# Main.net
KiCad netlist of a schematic drawn in Altium Designer
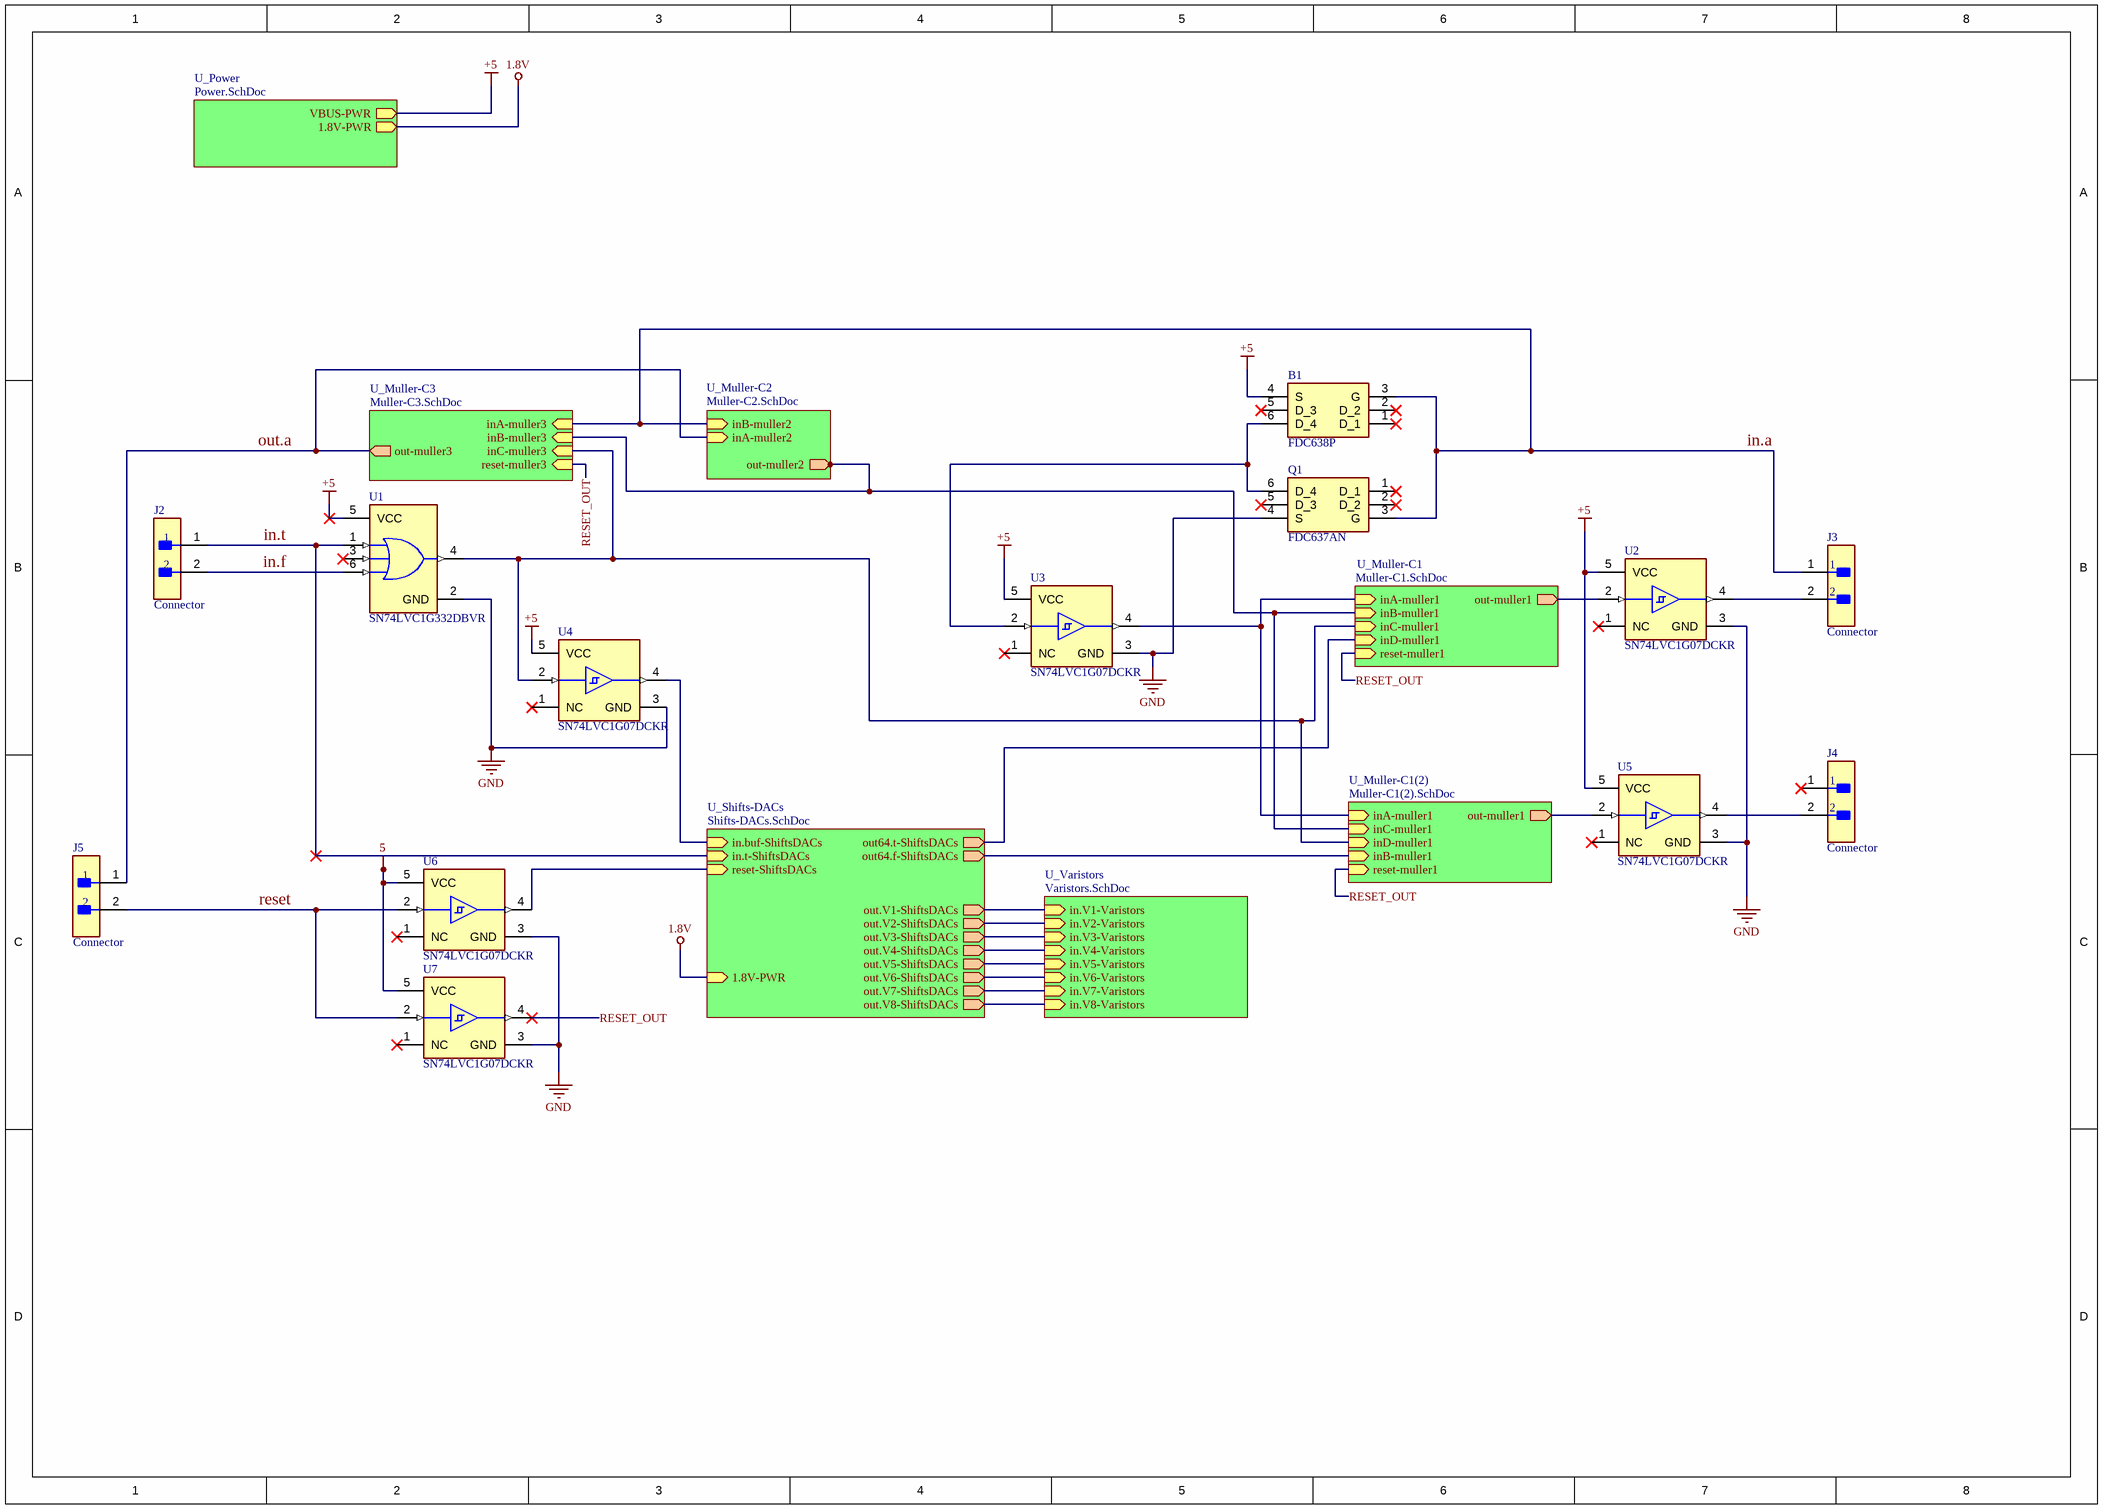
[diagram p0: Main.SchDoc]

(export (version "E")
  (design (tool "Eeschema 10.0.6"))
  (components
    (comp (ref "B1")
      (value "FDC638P")
      (footprint "SOT95P275X110-6N")
      (description "Low gate charge (10 nC typical)")
      (fields (field (name "MOUSER PART NUMBER") "512-FDC638P"))
      (libsource (lib "iloke") (part "FDC638P"))
    )
    (comp (ref "J2")
      (value "Connector")
      (footprint "FP-B2B-XH-A_LF_SN-MFG")
      (description "B2B-XH-A(LF)(SN) CONN HEADER VERT 2POS 2.5MM")
      (libsource (lib "") (part "3bc925449376181038e59eaffc5286c_1"))
    )
    (comp (ref "J3")
      (value "Connector")
      (footprint "FP-B2B-XH-A_LF_SN-MFG")
      (description "B2B-XH-A(LF)(SN) CONN HEADER VERT 2POS 2.5MM")
      (libsource (lib "Altium Content Vault") (part "3bc925449376181038e59eaffc5286c"))
    )
    (comp (ref "J4")
      (value "Connector")
      (footprint "FP-B2B-XH-A_LF_SN-MFG")
      (description "B2B-XH-A(LF)(SN) CONN HEADER VERT 2POS 2.5MM")
      (libsource (lib "Altium Content Vault") (part "3bc925449376181038e59eaffc5286c"))
    )
    (comp (ref "J5")
      (value "Connector")
      (footprint "FP-B2B-XH-A_LF_SN-MFG")
      (description "B2B-XH-A(LF)(SN) CONN HEADER VERT 2POS 2.5MM")
      (libsource (lib "") (part "3bc925449376181038e59eaffc5286c_1"))
    )
    (comp (ref "Q1")
      (value "FDC637AN")
      (footprint "SOT95P275X110-6N")
      (description "Low gate charge (10.5nC typical).")
      (fields (field (name "MOUSER PART NUMBER") "512-FDC637AN"))
      (libsource (lib "iloke") (part "FDC637AN"))
    )
    (comp (ref "U1")
      (value "SN74LVC1G332DBVR")
      (footprint "FP-DBV0006A-MFG")
      (description "IC GATE OR 1CH 3-INP SOT23-6")
      (fields
        (field (name "OCTOPART") "https://octopart.com/sn74lvc1g332dbvr-texas+instruments-464996")
        (field (name "MANUFACTURER") "TEXAS INSTRUMENTS")
      )
      (libsource (lib "Altium Content Vault") (part "9bd6587d4ded7f3f3ab4f7d0d680d6b"))
    )
    (comp (ref "U2")
      (value "SN74LVC1G07DCKR")
      (footprint "FP-DCK0005A-MFG")
      (description "Buffer, LVC/LCX/Z Series, 1-Func, 1-Input, CMOS, PDSO5")
      (libsource (lib "iloke") (part "8ab337023d36144ede9cc3383aed264"))
    )
    (comp (ref "U3")
      (value "SN74LVC1G07DCKR")
      (footprint "FP-DCK0005A-MFG")
      (description "Buffer, LVC/LCX/Z Series, 1-Func, 1-Input, CMOS, PDSO5")
      (libsource (lib "iloke") (part "8ab337023d36144ede9cc3383aed264"))
    )
    (comp (ref "U4")
      (value "SN74LVC1G07DCKR")
      (footprint "FP-DCK0005A-MFG")
      (description "Buffer, LVC/LCX/Z Series, 1-Func, 1-Input, CMOS, PDSO5")
      (libsource (lib "iloke") (part "8ab337023d36144ede9cc3383aed264"))
    )
    (comp (ref "U5")
      (value "SN74LVC1G07DCKR")
      (footprint "FP-DCK0005A-MFG")
      (description "Buffer, LVC/LCX/Z Series, 1-Func, 1-Input, CMOS, PDSO5")
      (libsource (lib "iloke") (part "8ab337023d36144ede9cc3383aed264"))
    )
    (comp (ref "U6")
      (value "SN74LVC1G07DCKR")
      (footprint "FP-DCK0005A-MFG")
      (description "Buffer, LVC/LCX/Z Series, 1-Func, 1-Input, CMOS, PDSO5")
      (libsource (lib "iloke") (part "8ab337023d36144ede9cc3383aed264"))
    )
    (comp (ref "U7")
      (value "SN74LVC1G07DCKR")
      (footprint "FP-DCK0005A-MFG")
      (description "Buffer, LVC/LCX/Z Series, 1-Func, 1-Input, CMOS, PDSO5")
      (libsource (lib "iloke") (part "8ab337023d36144ede9cc3383aed264"))
    )
  )
  (nets
    (net (code "1") (name "+5") (class "Default")
      (node (ref "B1") (pin "4") (pinfunction "S_4") (pintype "passive"))
      (node (ref "U1") (pin "5") (pinfunction "VCC_5") (pintype "power_in"))
      (node (ref "U2") (pin "5") (pinfunction "VCC_5") (pintype "power_in"))
      (node (ref "U3") (pin "5") (pinfunction "VCC_5") (pintype "power_in"))
      (node (ref "U4") (pin "5") (pinfunction "VCC_5") (pintype "power_in"))
      (node (ref "U5") (pin "5") (pinfunction "VCC_5") (pintype "power_in"))
    )
    (net (code "2") (name "/RESET_OUT") (class "Default")
      (node (ref "U7") (pin "4") (pinfunction "Y_4") (pintype "output"))
    )
    (net (code "3") (name "/in.a") (class "Default")
      (node (ref "B1") (pin "3") (pinfunction "G_3") (pintype "passive"))
      (node (ref "J3") (pin "1") (pinfunction "1_1") (pintype "passive"))
      (node (ref "Q1") (pin "3") (pinfunction "G_3") (pintype "passive"))
    )
    (net (code "4") (name "/in.buf-ShiftsDACs") (class "Default")
      (node (ref "U4") (pin "4") (pinfunction "Y_4") (pintype "output"))
    )
    (net (code "5") (name "/in.f") (class "Default")
      (node (ref "J2") (pin "2") (pinfunction "2_2") (pintype "passive"))
      (node (ref "U1") (pin "6") (pinfunction "C_6") (pintype "input"))
    )
    (net (code "6") (name "/in.t") (class "Default")
      (node (ref "J2") (pin "1") (pinfunction "1_1") (pintype "passive"))
      (node (ref "U1") (pin "1") (pinfunction "A_1") (pintype "input"))
    )
    (net (code "7") (name "/inA-muller1") (class "Default")
      (node (ref "U3") (pin "4") (pinfunction "Y_4") (pintype "output"))
    )
    (net (code "8") (name "/inC-muller1") (class "Default")
      (node (ref "U1") (pin "4") (pinfunction "Y_4") (pintype "output"))
      (node (ref "U4") (pin "2") (pinfunction "A_2") (pintype "input"))
    )
    (net (code "9") (name "/out-muller1") (class "Default")
      (node (ref "U2") (pin "2") (pinfunction "A_2") (pintype "input"))
    )
    (net (code "10") (name "/out-muller1_1") (class "Default")
      (node (ref "U5") (pin "2") (pinfunction "A_2") (pintype "input"))
    )
    (net (code "20") (name "/out.a") (class "Default")
      (node (ref "J5") (pin "1") (pinfunction "1_1") (pintype "passive"))
    )
    (net (code "23") (name "/reset") (class "Default")
      (node (ref "J5") (pin "2") (pinfunction "2_2") (pintype "passive"))
      (node (ref "U6") (pin "2") (pinfunction "A_2") (pintype "input"))
      (node (ref "U7") (pin "2") (pinfunction "A_2") (pintype "input"))
    )
    (net (code "24") (name "/reset-ShiftsDACs") (class "Default")
      (node (ref "U6") (pin "4") (pinfunction "Y_4") (pintype "output"))
    )
    (net (code "26") (name "5") (class "Default")
      (node (ref "U6") (pin "5") (pinfunction "VCC_5") (pintype "power_in"))
      (node (ref "U7") (pin "5") (pinfunction "VCC_5") (pintype "power_in"))
    )
    (net (code "27") (name "GND") (class "Default")
      (node (ref "Q1") (pin "4") (pinfunction "S_4") (pintype "passive"))
      (node (ref "U1") (pin "2") (pinfunction "GND_2") (pintype "power_in"))
      (node (ref "U2") (pin "3") (pinfunction "GND_3") (pintype "power_in"))
      (node (ref "U3") (pin "3") (pinfunction "GND_3") (pintype "power_in"))
      (node (ref "U4") (pin "3") (pinfunction "GND_3") (pintype "power_in"))
      (node (ref "U5") (pin "3") (pinfunction "GND_3") (pintype "power_in"))
      (node (ref "U6") (pin "3") (pinfunction "GND_3") (pintype "power_in"))
      (node (ref "U7") (pin "3") (pinfunction "GND_3") (pintype "power_in"))
    )
    (net (code "28") (name "Net-(B1-D_4)") (class "Default")
      (node (ref "B1") (pin "6") (pinfunction "D_4_6") (pintype "passive"))
      (node (ref "Q1") (pin "6") (pinfunction "D_4_6") (pintype "passive"))
      (node (ref "U3") (pin "2") (pinfunction "A_2") (pintype "input"))
    )
    (net (code "29") (name "Net-(U2-Y)") (class "Default")
      (node (ref "J3") (pin "2") (pinfunction "2_2") (pintype "passive"))
      (node (ref "U2") (pin "4") (pinfunction "Y_4") (pintype "output"))
    )
    (net (code "30") (name "Net-(U5-Y)") (class "Default")
      (node (ref "J4") (pin "2") (pinfunction "2_2") (pintype "passive"))
      (node (ref "U5") (pin "4") (pinfunction "Y_4") (pintype "output"))
    )
    (net (code "31") (name "unconnected-(B1-D_1-Pad1)") (class "Default")
      (node (ref "B1") (pin "1") (pinfunction "D_1_1") (pintype "passive+no_connect"))
    )
    (net (code "32") (name "unconnected-(B1-D_2-Pad2)") (class "Default")
      (node (ref "B1") (pin "2") (pinfunction "D_2_2") (pintype "passive+no_connect"))
    )
    (net (code "33") (name "unconnected-(B1-D_3-Pad5)") (class "Default")
      (node (ref "B1") (pin "5") (pinfunction "D_3_5") (pintype "passive+no_connect"))
    )
    (net (code "34") (name "unconnected-(J4-Pad1)") (class "Default")
      (node (ref "J4") (pin "1") (pinfunction "1_1") (pintype "passive+no_connect"))
    )
    (net (code "35") (name "unconnected-(Q1-D_1-Pad1)") (class "Default")
      (node (ref "Q1") (pin "1") (pinfunction "D_1_1") (pintype "passive+no_connect"))
    )
    (net (code "36") (name "unconnected-(Q1-D_2-Pad2)") (class "Default")
      (node (ref "Q1") (pin "2") (pinfunction "D_2_2") (pintype "passive+no_connect"))
    )
    (net (code "37") (name "unconnected-(Q1-D_3-Pad5)") (class "Default")
      (node (ref "Q1") (pin "5") (pinfunction "D_3_5") (pintype "passive+no_connect"))
    )
    (net (code "38") (name "unconnected-(U1-B-Pad3)") (class "Default")
      (node (ref "U1") (pin "3") (pinfunction "B_3") (pintype "input+no_connect"))
    )
    (net (code "39") (name "unconnected-(U2-NC-Pad1)") (class "Default")
      (node (ref "U2") (pin "1") (pinfunction "NC_1") (pintype "passive+no_connect"))
    )
    (net (code "40") (name "unconnected-(U3-NC-Pad1)") (class "Default")
      (node (ref "U3") (pin "1") (pinfunction "NC_1") (pintype "passive+no_connect"))
    )
    (net (code "41") (name "unconnected-(U4-NC-Pad1)") (class "Default")
      (node (ref "U4") (pin "1") (pinfunction "NC_1") (pintype "passive+no_connect"))
    )
    (net (code "42") (name "unconnected-(U5-NC-Pad1)") (class "Default")
      (node (ref "U5") (pin "1") (pinfunction "NC_1") (pintype "passive+no_connect"))
    )
    (net (code "43") (name "unconnected-(U6-NC-Pad1)") (class "Default")
      (node (ref "U6") (pin "1") (pinfunction "NC_1") (pintype "passive+no_connect"))
    )
    (net (code "44") (name "unconnected-(U7-NC-Pad1)") (class "Default")
      (node (ref "U7") (pin "1") (pinfunction "NC_1") (pintype "passive+no_connect"))
    )
  )
)
